# Pixel1_0_1.net
KiCad netlist of a schematic drawn in Altium Designer
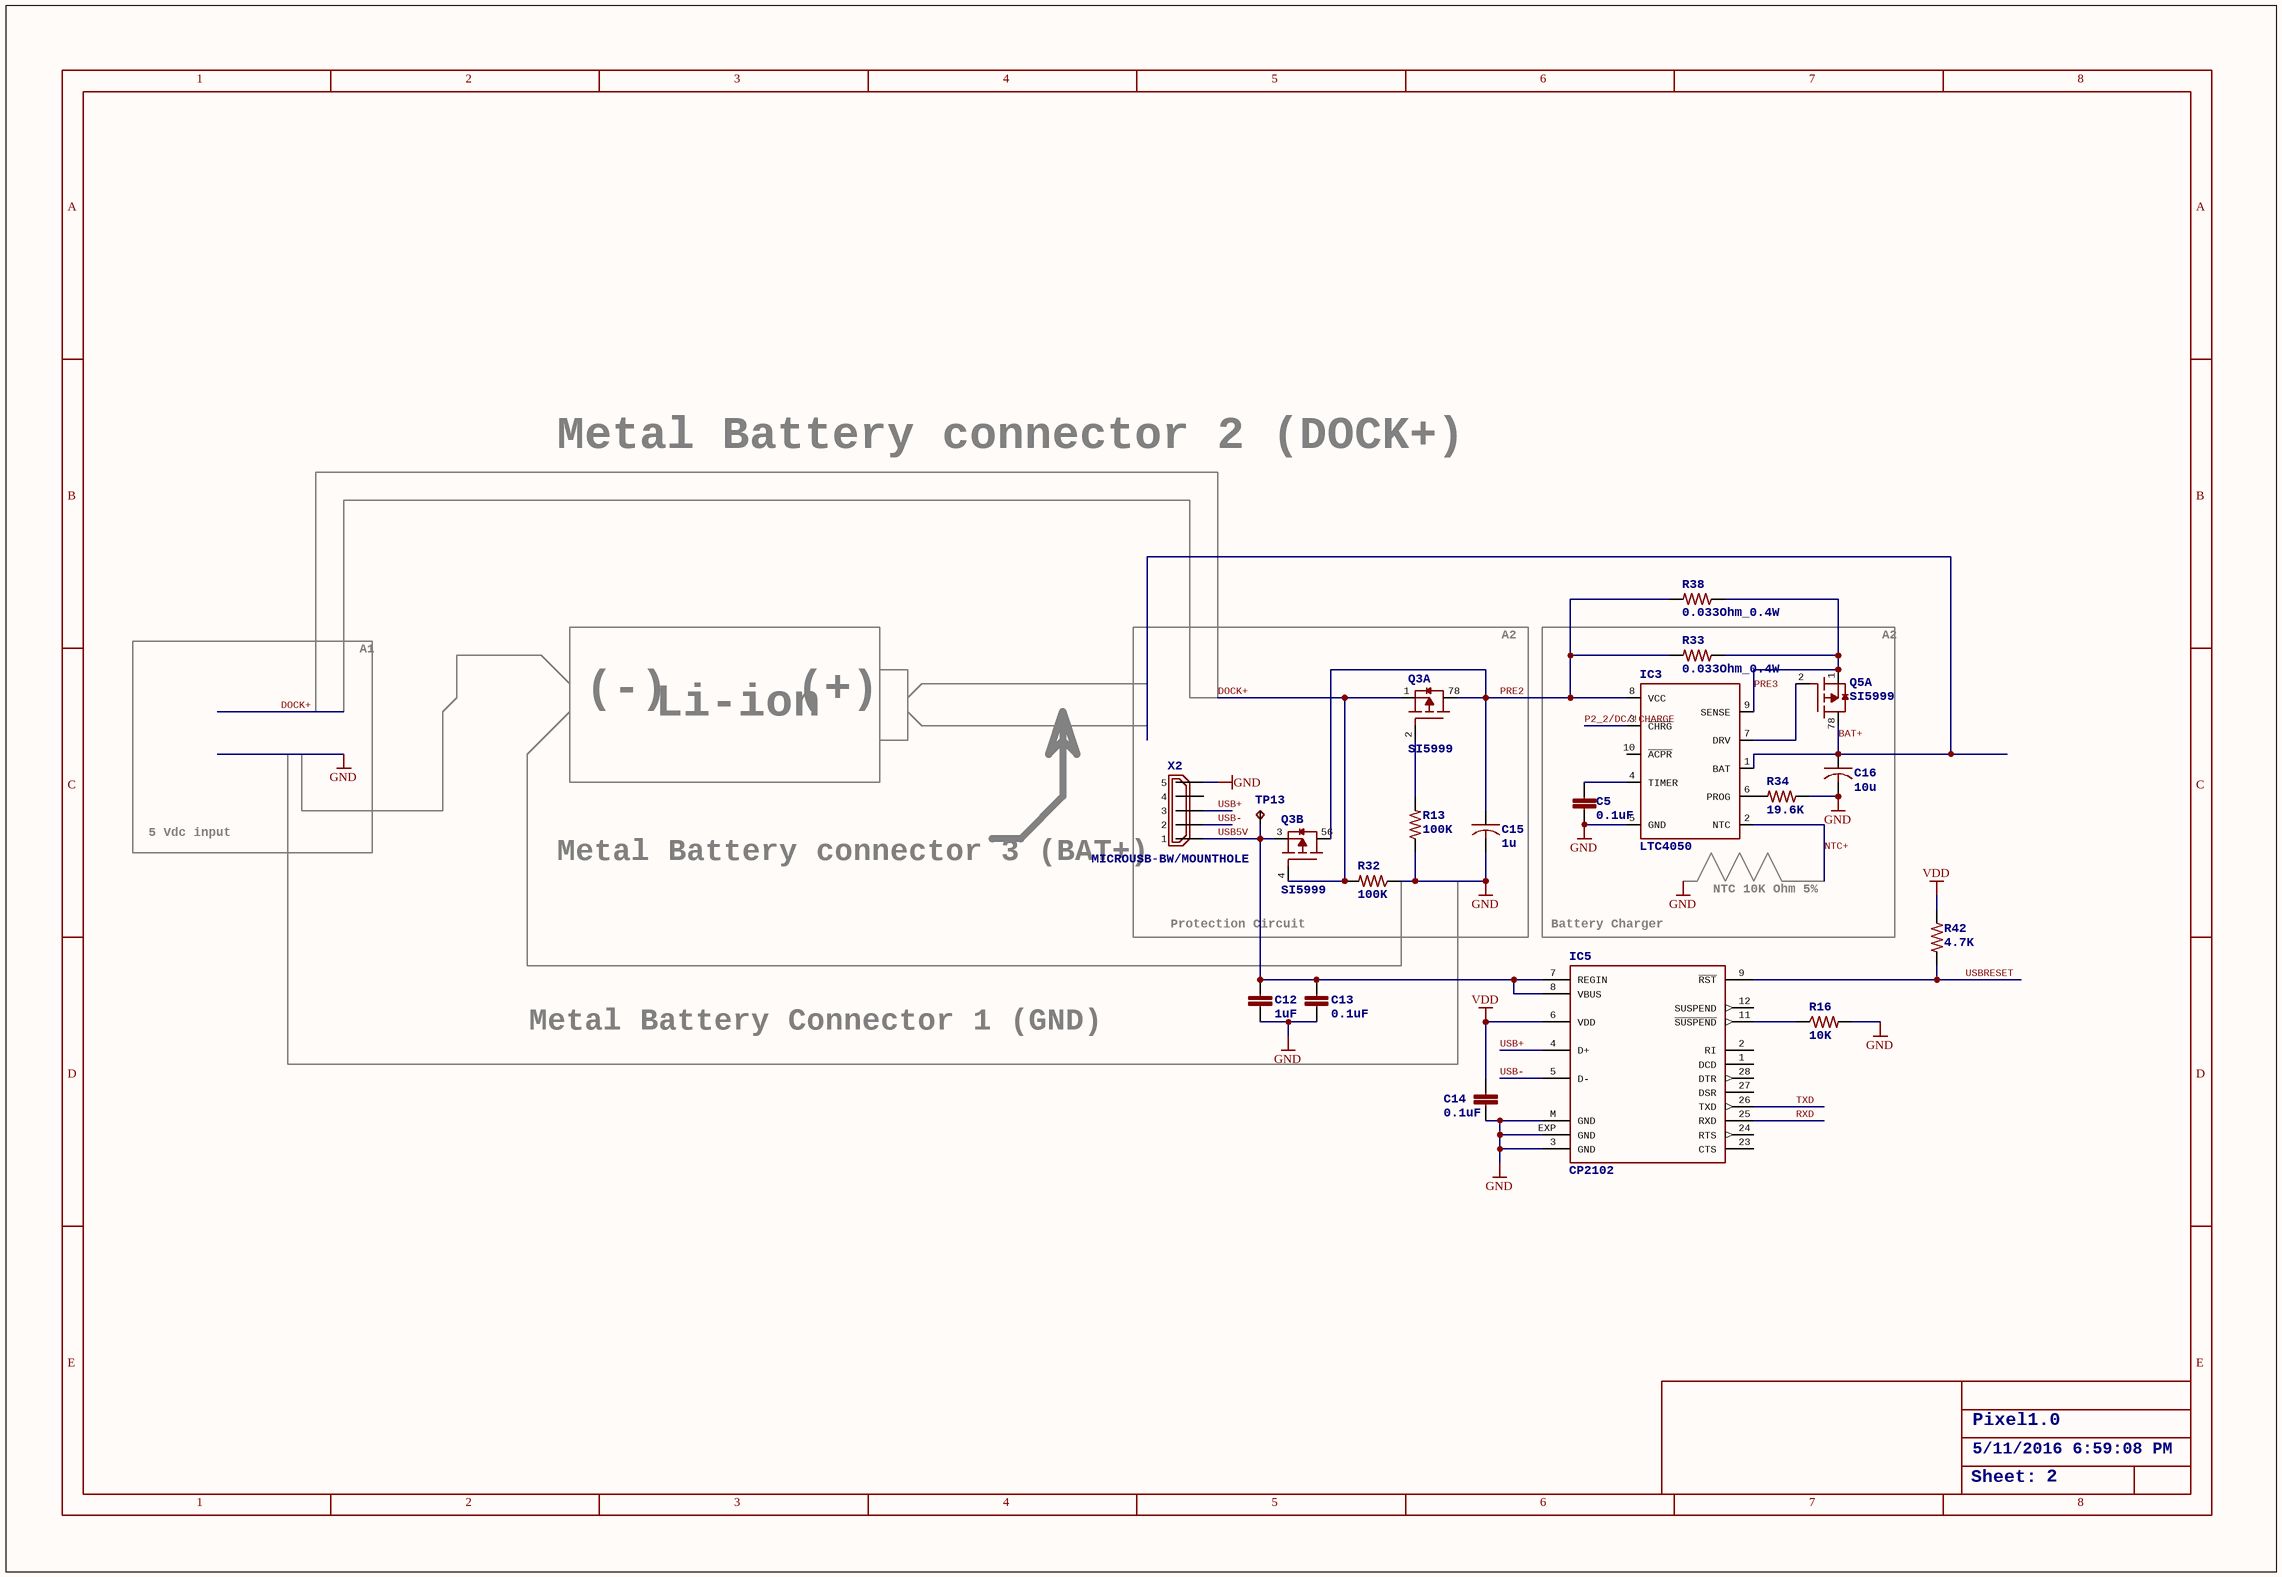
[diagram p0: Pixel1.0_1.SchDoc]

(export (version "E")
  (design (tool "Eeschema 10.0.6"))
  (components
    (comp (ref "C5")
      (value "0.1uF")
      (footprint "C0201")
      (description "CAPACITOR, European symbol")
      (libsource (lib "rcl") (part "C-EUC0201"))
    )
    (comp (ref "C12")
      (value "1uF")
      (footprint "C0201")
      (description "CAPACITOR, European symbol")
      (libsource (lib "rcl") (part "C-EUC0201"))
    )
    (comp (ref "C13")
      (value "0.1uF")
      (footprint "C0201")
      (description "CAPACITOR, European symbol")
      (libsource (lib "rcl") (part "C-EUC0201"))
    )
    (comp (ref "C14")
      (value "0.1uF")
      (footprint "C0201")
      (description "CAPACITOR, European symbol")
      (libsource (lib "rcl") (part "C-EUC0201"))
    )
    (comp (ref "C15")
      (value "1u")
      (footprint "C0201")
      (description "CAPACITOR, American symbol")
      (libsource (lib "rcl") (part "C-USC0201"))
    )
    (comp (ref "C16")
      (value "10u")
      (footprint "C0402")
      (description "CAPACITOR, American symbol")
      (libsource (lib "rcl") (part "C-USC0402"))
    )
    (comp (ref "IC3") (value "LTC4050") (footprint "MSOP10") (libsource (lib "vapeix") (part "LTC4050")))
    (comp (ref "IC5")
      (value "CP2102")
      (footprint "MLP28")
      (description "Single-Chip USB to UART Bridge   Source: www.silabs.com .. CP2101.pdf / cp2102.pdf")
      (fields (field (name "MF") "FARNELL") (field (name "MPN") "CP2102-GM"))
      (libsource (lib "silabs") (part "CP210*"))
    )
    (comp (ref "Q3")
      (value "SI5999")
      (footprint "1206-8CHIP-FET")
      (description "Dual N-Channel 30-V (D-S) MOSFET   Source: http://www.vishay.com/docs/71053/71053.pdf")
      (libsource (lib "Pixel1.0") (part "SI5999"))
    )
    (comp (ref "Q5")
      (value "SI5999")
      (footprint "1206-8CHIP-FET")
      (description "Dual N-Channel 30-V (D-S) MOSFET   Source: http://www.vishay.com/docs/71053/71053.pdf")
      (libsource (lib "Pixel1.0") (part "SI5999"))
    )
    (comp (ref "R13")
      (value "100K")
      (footprint "R0201")
      (description "RESISTOR, American symbol")
      (libsource (lib "rcl") (part "R-US_R0201"))
    )
    (comp (ref "R16")
      (value "10K")
      (footprint "R0201")
      (description "RESISTOR, American symbol")
      (libsource (lib "rcl") (part "R-US_R0201"))
    )
    (comp (ref "R32")
      (value "100K")
      (footprint "R0201")
      (description "RESISTOR, American symbol")
      (libsource (lib "rcl") (part "R-US_R0201"))
    )
    (comp (ref "R33")
      (value "0.033Ohm_0.4W")
      (footprint "R0603")
      (description "RESISTOR, American symbol")
      (libsource (lib "rcl") (part "R-US_R0603"))
    )
    (comp (ref "R34")
      (value "19.6K")
      (footprint "R0201")
      (description "RESISTOR, American symbol")
      (libsource (lib "rcl") (part "R-US_R0201"))
    )
    (comp (ref "R38")
      (value "0.033Ohm_0.4W")
      (footprint "R0603")
      (description "RESISTOR, American symbol")
      (libsource (lib "rcl") (part "R-US_R0603"))
    )
    (comp (ref "R42")
      (value "4.7K")
      (footprint "R0201")
      (description "RESISTOR, American symbol")
      (libsource (lib "rcl") (part "R-US_R0201"))
    )
    (comp (ref "TP13")
      (value "TPTP06R")
      (footprint "TP06R")
      (description "Test pad")
      (libsource (lib "testpad") (part "TPTP06R"))
    )
    (comp (ref "X2")
      (value "MICROUSB-BW/MOUNTHOLE")
      (footprint "MICRO_USB_B")
      (libsource (lib "vapeix") (part "MICROUSB-BW/MOUNTHOLE"))
    )
  )
  (nets
    (net (code "1") (name "/BAT+") (class "Default")
      (node (ref "C16") (pin "1") (pinfunction "1_1") (pintype "passive"))
      (node (ref "IC3") (pin "1") (pinfunction "BAT_1") (pintype "passive"))
      (node (ref "Q5") (pin "78") (pinfunction "D1_78") (pintype "passive"))
    )
    (net (code "2") (name "/DOCK+") (class "Default")
      (node (ref "Q3") (pin "1") (pinfunction "S1_1") (pintype "passive"))
      (node (ref "Q3") (pin "4") (pinfunction "G2_4") (pintype "passive"))
      (node (ref "R32") (pin "2") (pinfunction "2_2") (pintype "passive"))
    )
    (net (code "3") (name "/NTC+") (class "Default")
      (node (ref "IC3") (pin "2") (pinfunction "NTC_2") (pintype "passive"))
    )
    (net (code "4") (name "/P2_2{slash}DC{slash}!CHARGE") (class "Default")
      (node (ref "IC3") (pin "3") (pinfunction "~{CHRG}_3") (pintype "open_collector"))
    )
    (net (code "5") (name "/PRE2") (class "Default")
      (node (ref "C15") (pin "1") (pinfunction "1_1") (pintype "passive"))
      (node (ref "IC3") (pin "8") (pinfunction "VCC_8") (pintype "power_in"))
      (node (ref "Q3") (pin "56") (pinfunction "D2_56") (pintype "passive"))
      (node (ref "Q3") (pin "78") (pinfunction "D1_78") (pintype "passive"))
      (node (ref "R33") (pin "2") (pinfunction "2_2") (pintype "passive"))
      (node (ref "R38") (pin "2") (pinfunction "2_2") (pintype "passive"))
    )
    (net (code "6") (name "/PRE3") (class "Default")
      (node (ref "IC3") (pin "9") (pinfunction "SENSE_9") (pintype "open_collector"))
      (node (ref "Q5") (pin "1") (pinfunction "S1_1") (pintype "passive"))
      (node (ref "R33") (pin "1") (pinfunction "1_1") (pintype "passive"))
      (node (ref "R38") (pin "1") (pinfunction "1_1") (pintype "passive"))
    )
    (net (code "7") (name "/RXD") (class "Default")
      (node (ref "IC5") (pin "25") (pinfunction "RXD_25") (pintype "passive"))
    )
    (net (code "8") (name "/TXD") (class "Default")
      (node (ref "IC5") (pin "26") (pinfunction "TXD_26") (pintype "output"))
    )
    (net (code "9") (name "/USB+") (class "Default")
      (node (ref "IC5") (pin "4") (pinfunction "D+_4") (pintype "passive"))
      (node (ref "X2") (pin "P$3") (pinfunction "3_P$3") (pintype "passive"))
    )
    (net (code "10") (name "/USB-") (class "Default")
      (node (ref "IC5") (pin "5") (pinfunction "D-_5") (pintype "passive"))
      (node (ref "X2") (pin "P$2") (pinfunction "2_P$2") (pintype "passive"))
    )
    (net (code "11") (name "/USB5V") (class "Default")
      (node (ref "C12") (pin "1") (pinfunction "1_1") (pintype "passive"))
      (node (ref "C13") (pin "1") (pinfunction "1_1") (pintype "passive"))
      (node (ref "IC5") (pin "7") (pinfunction "REGIN_7") (pintype "passive"))
      (node (ref "IC5") (pin "8") (pinfunction "VBUS_8") (pintype "passive"))
      (node (ref "Q3") (pin "3") (pinfunction "S2_3") (pintype "passive"))
      (node (ref "TP13") (pin "TP") (pinfunction "TP_TP") (pintype "passive"))
      (node (ref "X2") (pin "P$1") (pinfunction "1_P$1") (pintype "passive"))
    )
    (net (code "12") (name "/USBRESET") (class "Default")
      (node (ref "IC5") (pin "9") (pinfunction "~{RST}_9") (pintype "passive"))
      (node (ref "R42") (pin "2") (pinfunction "2_2") (pintype "passive"))
    )
    (net (code "13") (name "GND") (class "Default")
      (node (ref "C12") (pin "2") (pinfunction "2_2") (pintype "passive"))
      (node (ref "C13") (pin "2") (pinfunction "2_2") (pintype "passive"))
      (node (ref "C14") (pin "2") (pinfunction "2_2") (pintype "passive"))
      (node (ref "C15") (pin "2") (pinfunction "2_2") (pintype "passive"))
      (node (ref "C16") (pin "2") (pinfunction "2_2") (pintype "passive"))
      (node (ref "C5") (pin "2") (pinfunction "2_2") (pintype "passive"))
      (node (ref "IC3") (pin "5") (pinfunction "GND_5") (pintype "power_in"))
      (node (ref "IC5") (pin "3") (pinfunction "GND_3") (pintype "power_in"))
      (node (ref "IC5") (pin "EXP") (pinfunction "GND_EXP") (pintype "power_in"))
      (node (ref "IC5") (pin "M") (pinfunction "GND_M") (pintype "power_in"))
      (node (ref "R13") (pin "1") (pinfunction "1_1") (pintype "passive"))
      (node (ref "R16") (pin "2") (pinfunction "2_2") (pintype "passive"))
      (node (ref "R32") (pin "1") (pinfunction "1_1") (pintype "passive"))
      (node (ref "R34") (pin "1") (pinfunction "1_1") (pintype "passive"))
      (node (ref "X2") (pin "P$5") (pinfunction "5_P$5") (pintype "passive"))
    )
    (net (code "14") (name "Net-(IC3-DRV)") (class "Default")
      (node (ref "IC3") (pin "7") (pinfunction "DRV_7") (pintype "passive"))
      (node (ref "Q5") (pin "2") (pinfunction "G1_2") (pintype "passive"))
    )
    (net (code "15") (name "Net-(IC3-PROG)") (class "Default")
      (node (ref "IC3") (pin "6") (pinfunction "PROG_6") (pintype "passive"))
      (node (ref "R34") (pin "2") (pinfunction "2_2") (pintype "passive"))
    )
    (net (code "16") (name "Net-(IC3-TIMER)") (class "Default")
      (node (ref "C5") (pin "1") (pinfunction "1_1") (pintype "passive"))
      (node (ref "IC3") (pin "4") (pinfunction "TIMER_4") (pintype "passive"))
    )
    (net (code "17") (name "Net-(IC5-~{SUSPEND})") (class "Default")
      (node (ref "IC5") (pin "11") (pinfunction "~{SUSPEND}_11") (pintype "output"))
      (node (ref "R16") (pin "1") (pinfunction "1_1") (pintype "passive"))
    )
    (net (code "18") (name "Net-(Q3A-G1)") (class "Default")
      (node (ref "Q3") (pin "2") (pinfunction "G1_2") (pintype "passive"))
      (node (ref "R13") (pin "2") (pinfunction "2_2") (pintype "passive"))
    )
    (net (code "19") (name "VDD") (class "Default")
      (node (ref "C14") (pin "1") (pinfunction "1_1") (pintype "passive"))
      (node (ref "IC5") (pin "6") (pinfunction "VDD_6") (pintype "power_in"))
      (node (ref "R42") (pin "1") (pinfunction "1_1") (pintype "passive"))
    )
    (net (code "20") (name "unconnected-(IC3-~{ACPR}-Pad10)") (class "Default")
      (node (ref "IC3") (pin "10") (pinfunction "~{ACPR}_10") (pintype "passive"))
    )
    (net (code "21") (name "unconnected-(IC5-CTS-Pad23)") (class "Default")
      (node (ref "IC5") (pin "23") (pinfunction "CTS_23") (pintype "passive"))
    )
    (net (code "22") (name "unconnected-(IC5-DCD-Pad1)") (class "Default")
      (node (ref "IC5") (pin "1") (pinfunction "DCD_1") (pintype "passive"))
    )
    (net (code "23") (name "unconnected-(IC5-DSR-Pad27)") (class "Default")
      (node (ref "IC5") (pin "27") (pinfunction "DSR_27") (pintype "passive"))
    )
    (net (code "24") (name "unconnected-(IC5-DTR-Pad28)") (class "Default")
      (node (ref "IC5") (pin "28") (pinfunction "DTR_28") (pintype "output"))
    )
    (net (code "25") (name "unconnected-(IC5-RI-Pad2)") (class "Default")
      (node (ref "IC5") (pin "2") (pinfunction "RI_2") (pintype "passive"))
    )
    (net (code "26") (name "unconnected-(IC5-RTS-Pad24)") (class "Default")
      (node (ref "IC5") (pin "24") (pinfunction "RTS_24") (pintype "output"))
    )
    (net (code "27") (name "unconnected-(IC5-SUSPEND-Pad12)") (class "Default")
      (node (ref "IC5") (pin "12") (pinfunction "SUSPEND_12") (pintype "output"))
    )
    (net (code "28") (name "unconnected-(X2-4-PadP$4)") (class "Default")
      (node (ref "X2") (pin "P$4") (pinfunction "4_P$4") (pintype "passive"))
    )
  )
)
